# stepper_module.net
KiCad netlist of a schematic drawn in EAGLE
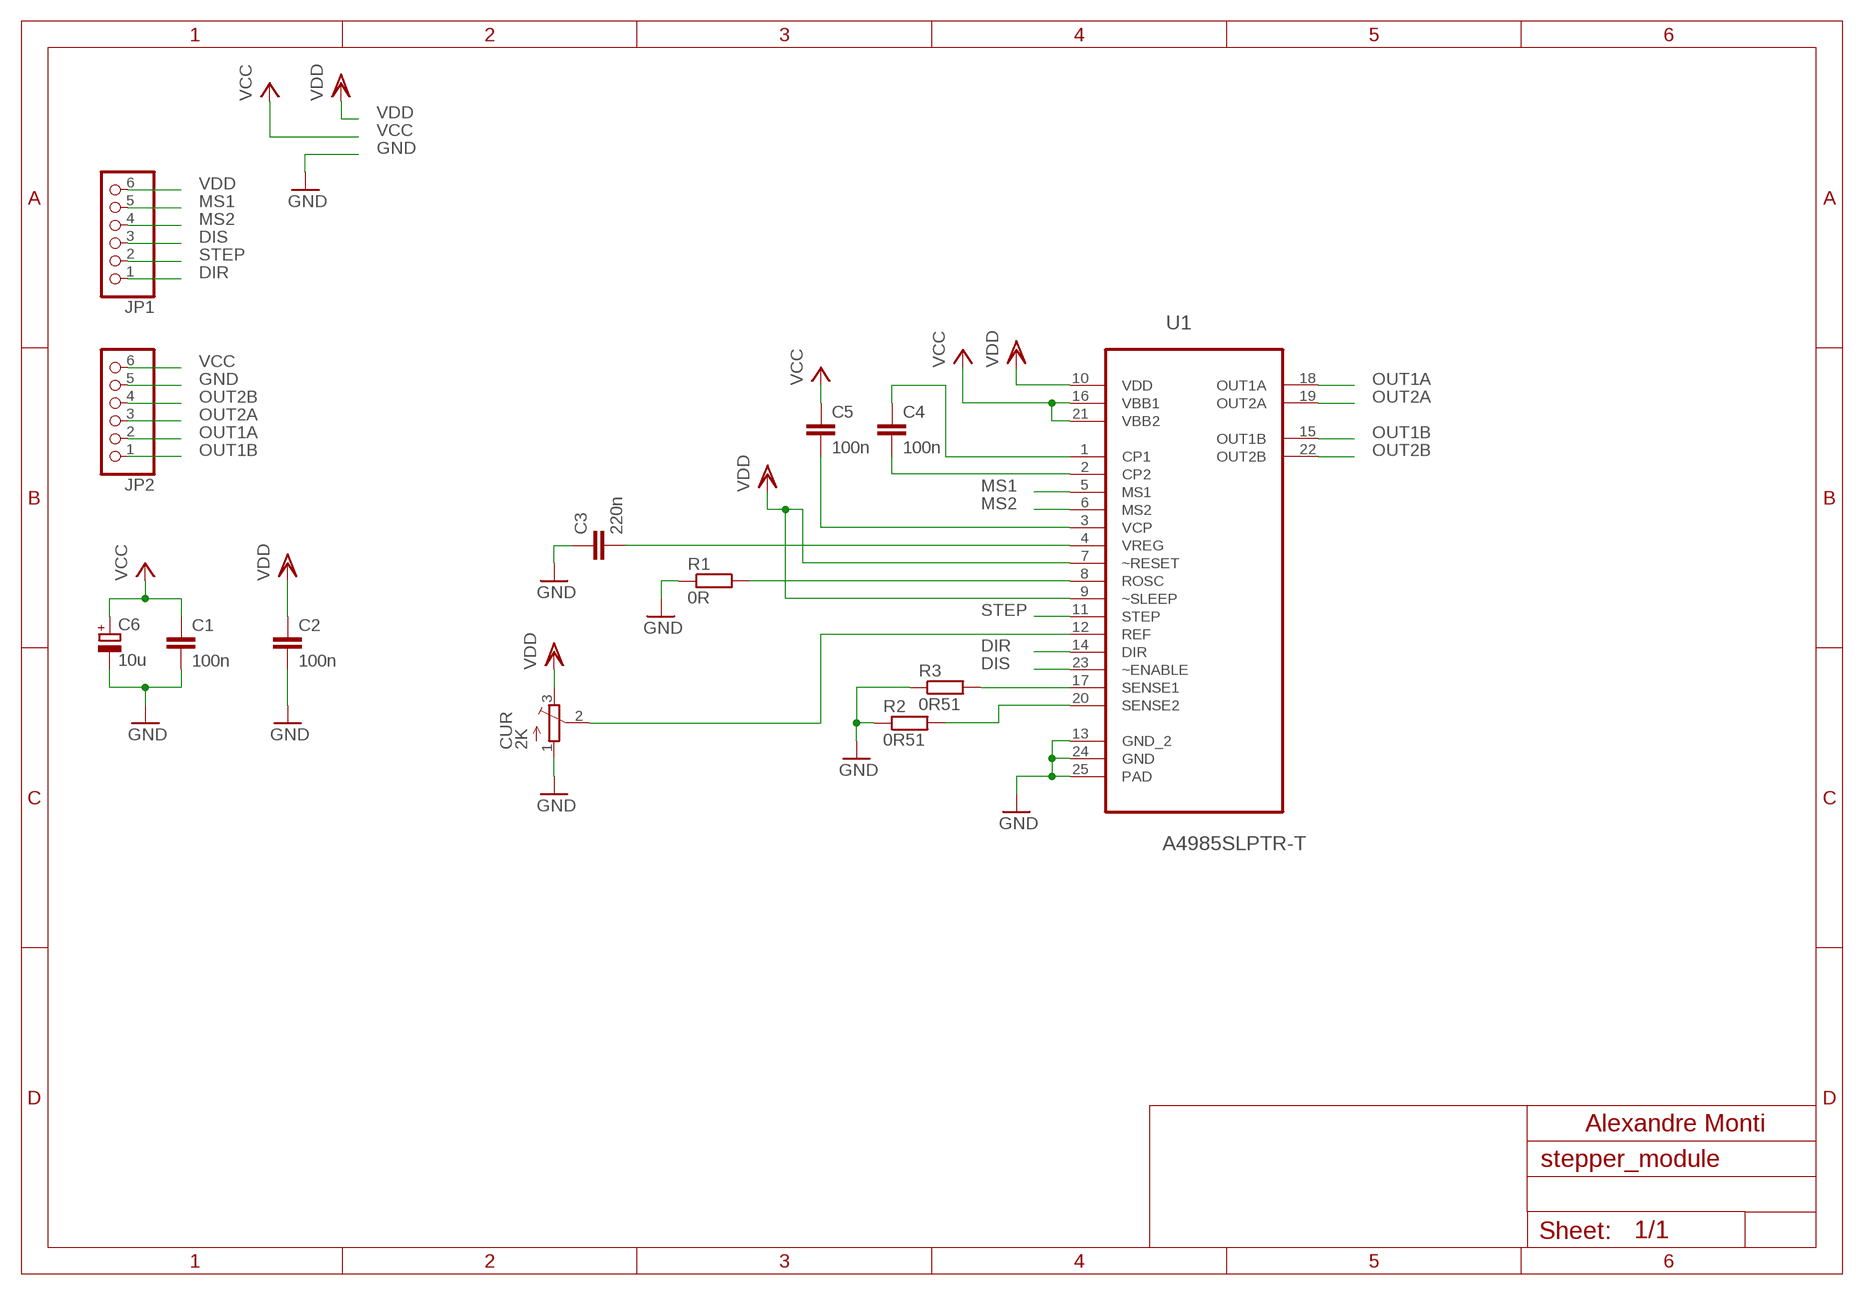
[diagram p0: schematic, sheet 1]

(export (version "E")
  (design (tool "Eeschema 10.0.6"))
  (components
    (comp (ref "C1")
      (value "100n")
      (footprint "eagle-import:C0805")
      (libsource (lib "eagle-import") (part "C-EUC0805"))
    )
    (comp (ref "C2")
      (value "100n")
      (footprint "eagle-import:C0805")
      (libsource (lib "eagle-import") (part "C-EUC0805"))
    )
    (comp (ref "C3")
      (value "220n")
      (footprint "eagle-import:C0805")
      (libsource (lib "eagle-import") (part "C-EUC0805"))
    )
    (comp (ref "C4")
      (value "100n")
      (footprint "eagle-import:C0805")
      (libsource (lib "eagle-import") (part "C-EUC0805"))
    )
    (comp (ref "C5")
      (value "100n")
      (footprint "eagle-import:C0805")
      (libsource (lib "eagle-import") (part "C-EUC0805"))
    )
    (comp (ref "C6")
      (value "10u")
      (footprint "eagle-import:SMC_B")
      (libsource (lib "eagle-import") (part "CPOL-EUSMCB"))
    )
    (comp (ref "CUR")
      (value "2K")
      (footprint "eagle-import:TC33X")
      (libsource (lib "eagle-import") (part "TRIMPOTTC33X"))
    )
    (comp (ref "JP1")
      (value "PINHD-1X6")
      (footprint "eagle-import:1X06")
      (libsource (lib "eagle-import") (part "PINHD-1X6"))
    )
    (comp (ref "JP2")
      (value "PINHD-1X6")
      (footprint "eagle-import:1X06")
      (libsource (lib "eagle-import") (part "PINHD-1X6"))
    )
    (comp (ref "R1")
      (value "0R")
      (footprint "eagle-import:R0805")
      (libsource (lib "eagle-import") (part "R-EU_R0805"))
    )
    (comp (ref "R2")
      (value "0R51")
      (footprint "eagle-import:R0805")
      (libsource (lib "eagle-import") (part "R-EU_R0805"))
    )
    (comp (ref "R3")
      (value "0R51")
      (footprint "eagle-import:R0805")
      (libsource (lib "eagle-import") (part "R-EU_R0805"))
    )
    (comp (ref "U1")
      (value "A4985SLPTR-T")
      (footprint "eagle-import:SOP65P640X120-25N")
      (fields (field (name "OC_FARNELL") "2057416"))
      (libsource (lib "eagle-import") (part "A4985SLPTR-T"))
    )
  )
  (nets
    (net (code "1") (name "/DIR") (class "Default")
      (node (ref "JP1") (pin "1") (pinfunction "1_1") (pintype "passive"))
      (node (ref "U1") (pin "14") (pinfunction "DIR_14") (pintype "input"))
    )
    (net (code "2") (name "/DIS") (class "Default")
      (node (ref "JP1") (pin "3") (pinfunction "3_3") (pintype "passive"))
      (node (ref "U1") (pin "23") (pinfunction "~{ENABLE}_23") (pintype "input"))
    )
    (net (code "3") (name "/MS1") (class "Default")
      (node (ref "JP1") (pin "5") (pinfunction "5_5") (pintype "passive"))
      (node (ref "U1") (pin "5") (pinfunction "MS1_5") (pintype "input"))
    )
    (net (code "4") (name "/MS2") (class "Default")
      (node (ref "JP1") (pin "4") (pinfunction "4_4") (pintype "passive"))
      (node (ref "U1") (pin "6") (pinfunction "MS2_6") (pintype "input"))
    )
    (net (code "5") (name "/OUT1A") (class "Default")
      (node (ref "JP2") (pin "2") (pinfunction "2_2") (pintype "passive"))
      (node (ref "U1") (pin "18") (pinfunction "OUT1A_18") (pintype "output"))
    )
    (net (code "6") (name "/OUT1B") (class "Default")
      (node (ref "JP2") (pin "1") (pinfunction "1_1") (pintype "passive"))
      (node (ref "U1") (pin "15") (pinfunction "OUT1B_15") (pintype "output"))
    )
    (net (code "7") (name "/OUT2A") (class "Default")
      (node (ref "JP2") (pin "3") (pinfunction "3_3") (pintype "passive"))
      (node (ref "U1") (pin "19") (pinfunction "OUT2A_19") (pintype "output"))
    )
    (net (code "8") (name "/OUT2B") (class "Default")
      (node (ref "JP2") (pin "4") (pinfunction "4_4") (pintype "passive"))
      (node (ref "U1") (pin "22") (pinfunction "OUT2B_22") (pintype "output"))
    )
    (net (code "9") (name "/STEP") (class "Default")
      (node (ref "JP1") (pin "2") (pinfunction "2_2") (pintype "passive"))
      (node (ref "U1") (pin "11") (pinfunction "STEP_11") (pintype "input"))
    )
    (net (code "10") (name "GND") (class "Default")
      (node (ref "C1") (pin "2") (pinfunction "2_2") (pintype "passive"))
      (node (ref "C2") (pin "2") (pinfunction "2_2") (pintype "passive"))
      (node (ref "C3") (pin "1") (pinfunction "1_1") (pintype "passive"))
      (node (ref "C6") (pin "-") (pinfunction "-_-") (pintype "passive"))
      (node (ref "CUR") (pin "1") (pinfunction "A_1") (pintype "passive"))
      (node (ref "JP2") (pin "5") (pinfunction "5_5") (pintype "passive"))
      (node (ref "R1") (pin "1") (pinfunction "1_1") (pintype "passive"))
      (node (ref "R2") (pin "1") (pinfunction "1_1") (pintype "passive"))
      (node (ref "R3") (pin "1") (pinfunction "1_1") (pintype "passive"))
      (node (ref "U1") (pin "13") (pinfunction "GND_2_13") (pintype "passive"))
      (node (ref "U1") (pin "24") (pinfunction "GND_24") (pintype "passive"))
      (node (ref "U1") (pin "25") (pinfunction "PAD_25") (pintype "passive"))
    )
    (net (code "11") (name "Net-(CUR-S)") (class "Default")
      (node (ref "CUR") (pin "2") (pinfunction "S_2") (pintype "passive"))
      (node (ref "U1") (pin "12") (pinfunction "REF_12") (pintype "input"))
    )
    (net (code "12") (name "Net-(U1-CP1)") (class "Default")
      (node (ref "C4") (pin "1") (pinfunction "1_1") (pintype "passive"))
      (node (ref "U1") (pin "1") (pinfunction "CP1_1") (pintype "passive"))
    )
    (net (code "13") (name "Net-(U1-CP2)") (class "Default")
      (node (ref "C4") (pin "2") (pinfunction "2_2") (pintype "passive"))
      (node (ref "U1") (pin "2") (pinfunction "CP2_2") (pintype "passive"))
    )
    (net (code "14") (name "Net-(U1-ROSC)") (class "Default")
      (node (ref "R1") (pin "2") (pinfunction "2_2") (pintype "passive"))
      (node (ref "U1") (pin "8") (pinfunction "ROSC_8") (pintype "input"))
    )
    (net (code "15") (name "Net-(U1-SENSE1)") (class "Default")
      (node (ref "R3") (pin "2") (pinfunction "2_2") (pintype "passive"))
      (node (ref "U1") (pin "17") (pinfunction "SENSE1_17") (pintype "input"))
    )
    (net (code "16") (name "Net-(U1-SENSE2)") (class "Default")
      (node (ref "R2") (pin "2") (pinfunction "2_2") (pintype "passive"))
      (node (ref "U1") (pin "20") (pinfunction "SENSE2_20") (pintype "input"))
    )
    (net (code "17") (name "Net-(U1-VCP)") (class "Default")
      (node (ref "C5") (pin "2") (pinfunction "2_2") (pintype "passive"))
      (node (ref "U1") (pin "3") (pinfunction "VCP_3") (pintype "passive"))
    )
    (net (code "18") (name "Net-(U1-VREG)") (class "Default")
      (node (ref "C3") (pin "2") (pinfunction "2_2") (pintype "passive"))
      (node (ref "U1") (pin "4") (pinfunction "VREG_4") (pintype "passive"))
    )
    (net (code "19") (name "VCC") (class "Default")
      (node (ref "C1") (pin "1") (pinfunction "1_1") (pintype "passive"))
      (node (ref "C5") (pin "1") (pinfunction "1_1") (pintype "passive"))
      (node (ref "C6") (pin "+") (pinfunction "+_+") (pintype "passive"))
      (node (ref "JP2") (pin "6") (pinfunction "6_6") (pintype "passive"))
      (node (ref "U1") (pin "16") (pinfunction "VBB1_16") (pintype "power_in"))
      (node (ref "U1") (pin "21") (pinfunction "VBB2_21") (pintype "power_in"))
    )
    (net (code "20") (name "VDD") (class "Default")
      (node (ref "C2") (pin "1") (pinfunction "1_1") (pintype "passive"))
      (node (ref "CUR") (pin "3") (pinfunction "E_3") (pintype "passive"))
      (node (ref "JP1") (pin "6") (pinfunction "6_6") (pintype "passive"))
      (node (ref "U1") (pin "10") (pinfunction "VDD_10") (pintype "power_in"))
      (node (ref "U1") (pin "7") (pinfunction "~{RESET}_7") (pintype "input"))
      (node (ref "U1") (pin "9") (pinfunction "~{SLEEP}_9") (pintype "input"))
    )
  )
)
